# U2S_HVPP.net
KiCad netlist of a schematic drawn in Altium Designer
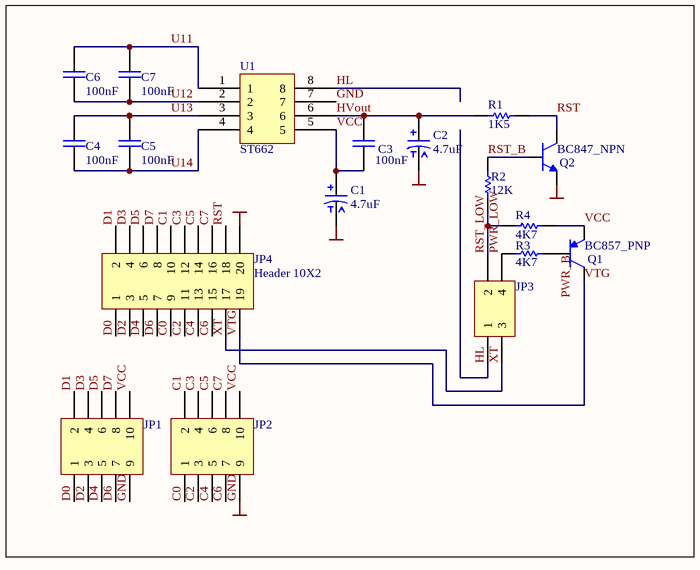
[diagram p0: U2S_HVPP.SchDoc]

(export (version "E")
  (design (tool "Eeschema 10.0.6"))
  (components
    (comp (ref "C1")
      (value "4.7uF")
      (footprint "TR3A")
      (fields (field (name "Comment") "Capacitor Ta"))
      (libsource (lib "MiscComponents") (part "Capacitor Ta"))
    )
    (comp (ref "C2")
      (value "4.7uF")
      (footprint "TR3A")
      (fields (field (name "Comment") "Capacitor Ta"))
      (libsource (lib "MiscComponents") (part "Capacitor Ta"))
    )
    (comp (ref "C3")
      (value "100nF")
      (footprint "SMD0603")
      (fields (field (name "Comment") "Capacitor"))
      (libsource (lib "MiscComponents") (part "Capacitor"))
    )
    (comp (ref "C4")
      (value "100nF")
      (footprint "SMD0603")
      (fields (field (name "Comment") "Capacitor"))
      (libsource (lib "MiscComponents") (part "Capacitor"))
    )
    (comp (ref "C5")
      (value "100nF")
      (footprint "SMD0603")
      (fields (field (name "Comment") "Capacitor"))
      (libsource (lib "MiscComponents") (part "Capacitor"))
    )
    (comp (ref "C6")
      (value "100nF")
      (footprint "SMD0603")
      (fields (field (name "Comment") "Capacitor"))
      (libsource (lib "MiscComponents") (part "Capacitor"))
    )
    (comp (ref "C7")
      (value "100nF")
      (footprint "SMD0603")
      (fields (field (name "Comment") "Capacitor"))
      (libsource (lib "MiscComponents") (part "Capacitor"))
    )
    (comp (ref "JP1")
      (value "Header 5X2")
      (footprint "HDR2X5")
      (description "Header, 5-Pin, Dual row")
      (fields (field (name "PUBLISHER") "Altium Limited"))
      (libsource (lib "Miscellaneous Connectors") (part "Header 5X2"))
    )
    (comp (ref "JP2")
      (value "Header 5X2")
      (footprint "HDR2X5")
      (description "Header, 5-Pin, Dual row")
      (fields (field (name "PUBLISHER") "Altium Limited"))
      (libsource (lib "Miscellaneous Connectors") (part "Header 5X2"))
    )
    (comp (ref "JP3")
      (value "Header 2X2")
      (footprint "HDR2X2")
      (description "Header, 2-Pin, Dual row")
      (fields (field (name "PUBLISHER") "Altium Limited"))
      (libsource (lib "Miscellaneous Connectors") (part "Header 2X2"))
    )
    (comp (ref "JP4")
      (value "Header 10X2")
      (footprint "HDR2X10")
      (description "Header, 10-Pin, Dual row")
      (fields (field (name "PUBLISHER") "Altium Limited"))
      (libsource (lib "Miscellaneous Connectors") (part "Header 10X2"))
    )
    (comp (ref "Q1")
      (value "BC857_PNP")
      (footprint "SOT23")
      (libsource (lib "MiscComponents") (part "Transistor_PNP"))
    )
    (comp (ref "Q2")
      (value "BC847_NPN")
      (footprint "SOT23")
      (libsource (lib "MiscComponents") (part "Transistor_NPN"))
    )
    (comp (ref "R1")
      (value "1K5")
      (footprint "SMD0805")
      (fields (field (name "Comment") "Resistor"))
      (libsource (lib "MiscComponents") (part "Resistor"))
    )
    (comp (ref "R2")
      (value "12K")
      (footprint "SMD0603")
      (fields (field (name "Comment") "Resistor"))
      (libsource (lib "MiscComponents") (part "Resistor"))
    )
    (comp (ref "R3")
      (value "4K7")
      (footprint "SMD0603")
      (fields (field (name "Comment") "Resistor"))
      (libsource (lib "MiscComponents") (part "Resistor"))
    )
    (comp (ref "R4")
      (value "4K7")
      (footprint "SMD0603")
      (fields (field (name "Comment") "Resistor"))
      (libsource (lib "MiscComponents") (part "Resistor"))
    )
    (comp (ref "U1") (value "ST662") (footprint "SO8") (libsource (lib "U2S_HVPP") (part "ST662")))
  )
  (nets
    (net (code "1") (name "/C0") (class "Default")
      (node (ref "JP2") (pin "1") (pinfunction "1_1") (pintype "passive"))
      (node (ref "JP4") (pin "9") (pinfunction "9_9") (pintype "passive"))
    )
    (net (code "2") (name "/C1") (class "Default")
      (node (ref "JP2") (pin "2") (pinfunction "2_2") (pintype "passive"))
      (node (ref "JP4") (pin "10") (pinfunction "10_10") (pintype "passive"))
    )
    (net (code "3") (name "/C2") (class "Default")
      (node (ref "JP2") (pin "3") (pinfunction "3_3") (pintype "passive"))
      (node (ref "JP4") (pin "11") (pinfunction "11_11") (pintype "passive"))
    )
    (net (code "4") (name "/C3") (class "Default")
      (node (ref "JP2") (pin "4") (pinfunction "4_4") (pintype "passive"))
      (node (ref "JP4") (pin "12") (pinfunction "12_12") (pintype "passive"))
    )
    (net (code "5") (name "/C4") (class "Default")
      (node (ref "JP2") (pin "5") (pinfunction "5_5") (pintype "passive"))
      (node (ref "JP4") (pin "13") (pinfunction "13_13") (pintype "passive"))
    )
    (net (code "6") (name "/C5") (class "Default")
      (node (ref "JP2") (pin "6") (pinfunction "6_6") (pintype "passive"))
      (node (ref "JP4") (pin "14") (pinfunction "14_14") (pintype "passive"))
    )
    (net (code "7") (name "/C6") (class "Default")
      (node (ref "JP2") (pin "7") (pinfunction "7_7") (pintype "passive"))
      (node (ref "JP4") (pin "15") (pinfunction "15_15") (pintype "passive"))
    )
    (net (code "8") (name "/C7") (class "Default")
      (node (ref "JP2") (pin "8") (pinfunction "8_8") (pintype "passive"))
      (node (ref "JP4") (pin "16") (pinfunction "16_16") (pintype "passive"))
    )
    (net (code "9") (name "/D0") (class "Default")
      (node (ref "JP1") (pin "1") (pinfunction "1_1") (pintype "passive"))
      (node (ref "JP4") (pin "1") (pinfunction "1_1") (pintype "passive"))
    )
    (net (code "10") (name "/D1") (class "Default")
      (node (ref "JP1") (pin "2") (pinfunction "2_2") (pintype "passive"))
      (node (ref "JP4") (pin "2") (pinfunction "2_2") (pintype "passive"))
    )
    (net (code "11") (name "/D2") (class "Default")
      (node (ref "JP1") (pin "3") (pinfunction "3_3") (pintype "passive"))
      (node (ref "JP4") (pin "3") (pinfunction "3_3") (pintype "passive"))
    )
    (net (code "12") (name "/D3") (class "Default")
      (node (ref "JP1") (pin "4") (pinfunction "4_4") (pintype "passive"))
      (node (ref "JP4") (pin "4") (pinfunction "4_4") (pintype "passive"))
    )
    (net (code "13") (name "/D4") (class "Default")
      (node (ref "JP1") (pin "5") (pinfunction "5_5") (pintype "passive"))
      (node (ref "JP4") (pin "5") (pinfunction "5_5") (pintype "passive"))
    )
    (net (code "14") (name "/D5") (class "Default")
      (node (ref "JP1") (pin "6") (pinfunction "6_6") (pintype "passive"))
      (node (ref "JP4") (pin "6") (pinfunction "6_6") (pintype "passive"))
    )
    (net (code "15") (name "/D6") (class "Default")
      (node (ref "JP1") (pin "7") (pinfunction "7_7") (pintype "passive"))
      (node (ref "JP4") (pin "7") (pinfunction "7_7") (pintype "passive"))
    )
    (net (code "16") (name "/D7") (class "Default")
      (node (ref "JP1") (pin "8") (pinfunction "8_8") (pintype "passive"))
      (node (ref "JP4") (pin "8") (pinfunction "8_8") (pintype "passive"))
    )
    (net (code "17") (name "/HL") (class "Default")
      (node (ref "JP3") (pin "1") (pinfunction "1_1") (pintype "passive"))
      (node (ref "U1") (pin "8") (pinfunction "8_8") (pintype "passive"))
    )
    (net (code "18") (name "/HVout") (class "Default")
      (node (ref "C2") (pin "1") (pinfunction "1_1") (pintype "passive"))
      (node (ref "C3") (pin "2") (pinfunction "2_2") (pintype "passive"))
      (node (ref "R1") (pin "1") (pinfunction "1_1") (pintype "passive"))
      (node (ref "U1") (pin "6") (pinfunction "6_6") (pintype "passive"))
    )
    (net (code "19") (name "/PWR_B") (class "Default")
      (node (ref "Q1") (pin "B") (pinfunction "B_B") (pintype "passive"))
      (node (ref "R3") (pin "2") (pinfunction "2_2") (pintype "passive"))
    )
    (net (code "20") (name "/PWR_LOW") (class "Default")
      (node (ref "JP3") (pin "4") (pinfunction "4_4") (pintype "passive"))
      (node (ref "R3") (pin "1") (pinfunction "1_1") (pintype "passive"))
    )
    (net (code "21") (name "/RST") (class "Default")
      (node (ref "JP4") (pin "18") (pinfunction "18_18") (pintype "passive"))
      (node (ref "Q2") (pin "C") (pinfunction "C_C") (pintype "passive"))
      (node (ref "R1") (pin "2") (pinfunction "2_2") (pintype "passive"))
    )
    (net (code "22") (name "/RST_B") (class "Default")
      (node (ref "Q2") (pin "B") (pinfunction "B_B") (pintype "passive"))
      (node (ref "R2") (pin "2") (pinfunction "2_2") (pintype "passive"))
    )
    (net (code "23") (name "/RST_LOW") (class "Default")
      (node (ref "JP3") (pin "2") (pinfunction "2_2") (pintype "passive"))
      (node (ref "R2") (pin "1") (pinfunction "1_1") (pintype "passive"))
      (node (ref "R4") (pin "2") (pinfunction "2_2") (pintype "passive"))
    )
    (net (code "24") (name "/U11") (class "Default")
      (node (ref "C6") (pin "1") (pinfunction "1_1") (pintype "passive"))
      (node (ref "C7") (pin "2") (pinfunction "2_2") (pintype "passive"))
      (node (ref "U1") (pin "1") (pinfunction "1_1") (pintype "passive"))
    )
    (net (code "25") (name "/U12") (class "Default")
      (node (ref "C6") (pin "2") (pinfunction "2_2") (pintype "passive"))
      (node (ref "C7") (pin "1") (pinfunction "1_1") (pintype "passive"))
      (node (ref "U1") (pin "2") (pinfunction "2_2") (pintype "passive"))
    )
    (net (code "26") (name "/U13") (class "Default")
      (node (ref "C4") (pin "2") (pinfunction "2_2") (pintype "passive"))
      (node (ref "C5") (pin "2") (pinfunction "2_2") (pintype "passive"))
      (node (ref "U1") (pin "3") (pinfunction "3_3") (pintype "passive"))
    )
    (net (code "27") (name "/U14") (class "Default")
      (node (ref "C4") (pin "1") (pinfunction "1_1") (pintype "passive"))
      (node (ref "C5") (pin "1") (pinfunction "1_1") (pintype "passive"))
      (node (ref "U1") (pin "4") (pinfunction "4_4") (pintype "passive"))
    )
    (net (code "28") (name "/VCC") (class "Default")
      (node (ref "C1") (pin "1") (pinfunction "1_1") (pintype "passive"))
      (node (ref "C3") (pin "1") (pinfunction "1_1") (pintype "passive"))
      (node (ref "JP1") (pin "10") (pinfunction "10_10") (pintype "passive"))
      (node (ref "JP2") (pin "10") (pinfunction "10_10") (pintype "passive"))
      (node (ref "Q1") (pin "E") (pinfunction "E_E") (pintype "passive"))
      (node (ref "R4") (pin "1") (pinfunction "1_1") (pintype "passive"))
      (node (ref "U1") (pin "5") (pinfunction "5_5") (pintype "passive"))
    )
    (net (code "29") (name "/VTG") (class "Default")
      (node (ref "JP4") (pin "19") (pinfunction "19_19") (pintype "passive"))
      (node (ref "Q1") (pin "C") (pinfunction "C_C") (pintype "passive"))
    )
    (net (code "30") (name "/XT") (class "Default")
      (node (ref "JP3") (pin "3") (pinfunction "3_3") (pintype "passive"))
      (node (ref "JP4") (pin "17") (pinfunction "17_17") (pintype "passive"))
    )
    (net (code "31") (name "GND") (class "Default")
      (node (ref "C1") (pin "2") (pinfunction "2_2") (pintype "passive"))
      (node (ref "C2") (pin "2") (pinfunction "2_2") (pintype "passive"))
      (node (ref "JP1") (pin "9") (pinfunction "9_9") (pintype "passive"))
      (node (ref "JP2") (pin "9") (pinfunction "9_9") (pintype "passive"))
      (node (ref "JP4") (pin "20") (pinfunction "20_20") (pintype "passive"))
      (node (ref "Q2") (pin "E") (pinfunction "E_E") (pintype "passive"))
      (node (ref "U1") (pin "7") (pinfunction "7_7") (pintype "passive"))
    )
  )
)
